# ESPRobotCar.net
KiCad netlist of a schematic drawn in EAGLE
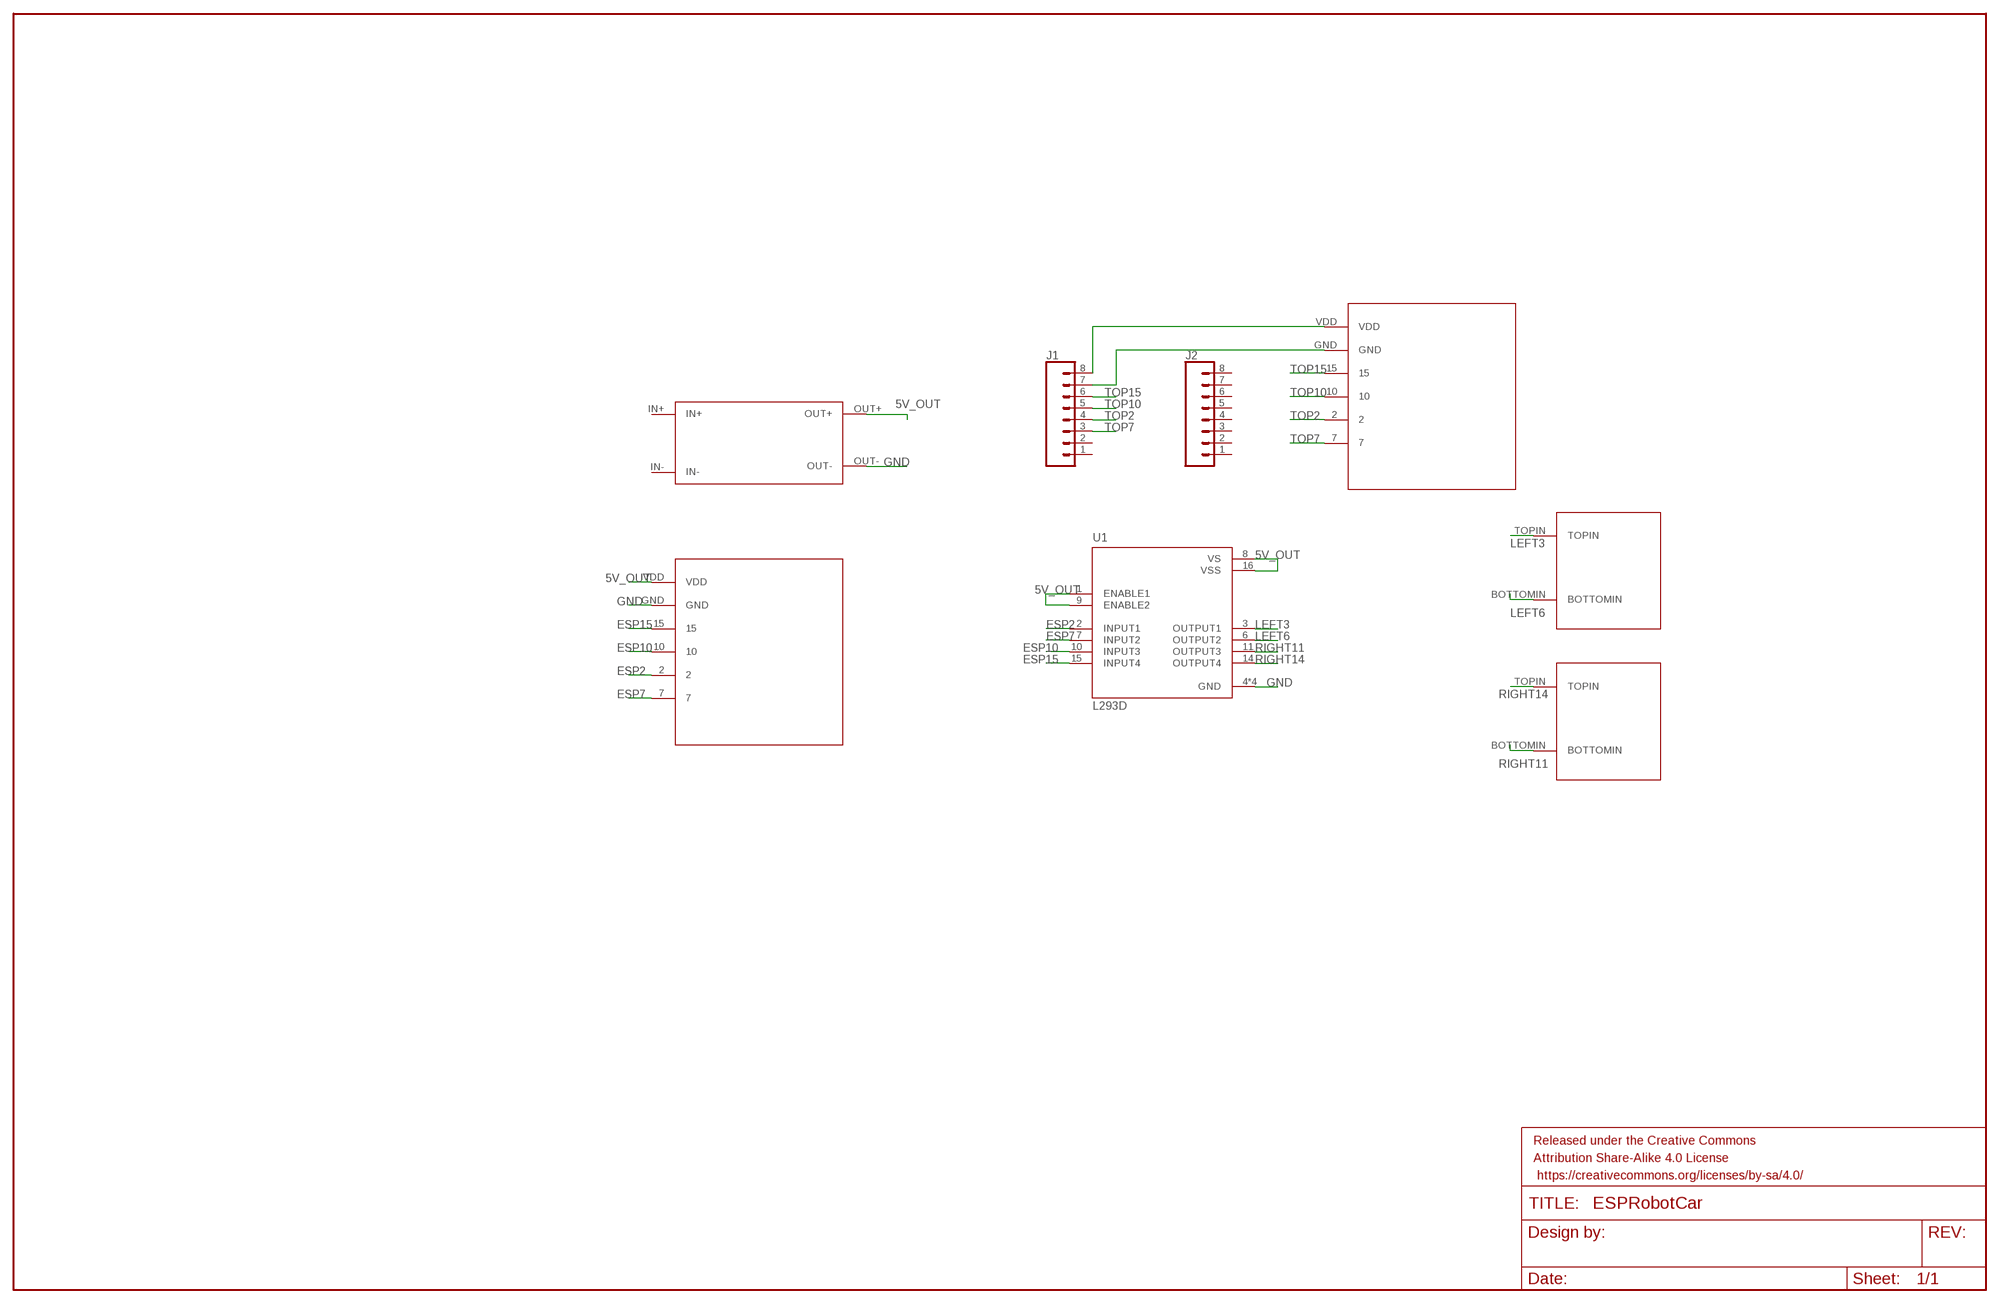
[diagram p0: schematic, sheet 1]

(export (version "E")
  (design (tool "Eeschema 10.0.6"))
  (components
    (comp (ref "FRAME1")
      (value "FRAME-LEDGER")
      (footprint "eagle-import:CREATIVE_COMMONS")
      (libsource (lib "eagle-import") (part "FRAME-LEDGER"))
    )
    (comp (ref "J1")
      (value "CONN_08\"")
      (footprint "eagle-import:1X08")
      (libsource (lib "eagle-import") (part "CONN_08{dblquote}"))
    )
    (comp (ref "J2")
      (value "CONN_08\"")
      (footprint "eagle-import:1X08")
      (libsource (lib "eagle-import") (part "CONN_08{dblquote}"))
    )
    (comp (ref "U$1")
      (value "DC_TO_DC")
      (footprint "eagle-import:DCTODC")
      (libsource (lib "eagle-import") (part "DC_TO_DC"))
    )
    (comp (ref "U$2")
      (value "MOTORPAD")
      (footprint "eagle-import:MOTORPAD")
      (libsource (lib "eagle-import") (part "MOTORPAD"))
    )
    (comp (ref "U$3")
      (value "MOTORPAD")
      (footprint "eagle-import:MOTORPAD")
      (libsource (lib "eagle-import") (part "MOTORPAD"))
    )
    (comp (ref "U$4")
      (value "MOTORBREAK")
      (footprint "eagle-import:MOTORBREAK")
      (libsource (lib "eagle-import") (part "MOTORBREAK"))
    )
    (comp (ref "U$5")
      (value "MOTORBREAK")
      (footprint "eagle-import:MOTORBREAK")
      (libsource (lib "eagle-import") (part "MOTORBREAK"))
    )
    (comp (ref "U1")
      (value "L293D")
      (footprint "eagle-import:DIP880W50P254L2000H510Q16")
      (fields (field (name "MF") "STMicroelectronics"))
      (libsource (lib "eagle-import") (part "L293D"))
    )
  )
  (nets
    (net (code "1") (name "/5V_OUT") (class "Default")
      (node (ref "U$1") (pin "OUT+") (pinfunction "OUT+_OUT+") (pintype "bidirectional"))
      (node (ref "U$4") (pin "VDD") (pinfunction "VDD_VDD") (pintype "bidirectional"))
      (node (ref "U1") (pin "1") (pinfunction "ENABLE1_1") (pintype "input"))
      (node (ref "U1") (pin "16") (pinfunction "VSS_16") (pintype "power_in"))
      (node (ref "U1") (pin "8") (pinfunction "VS_8") (pintype "power_in"))
      (node (ref "U1") (pin "9") (pinfunction "ENABLE2_9") (pintype "input"))
    )
    (net (code "2") (name "/ESP2") (class "Default")
      (node (ref "U$4") (pin "2") (pinfunction "2_2") (pintype "bidirectional"))
      (node (ref "U1") (pin "2") (pinfunction "INPUT1_2") (pintype "input"))
    )
    (net (code "3") (name "/ESP7") (class "Default")
      (node (ref "U$4") (pin "7") (pinfunction "7_7") (pintype "bidirectional"))
      (node (ref "U1") (pin "7") (pinfunction "INPUT2_7") (pintype "input"))
    )
    (net (code "4") (name "/ESP10") (class "Default")
      (node (ref "U$4") (pin "10") (pinfunction "10_10") (pintype "bidirectional"))
      (node (ref "U1") (pin "10") (pinfunction "INPUT3_10") (pintype "input"))
    )
    (net (code "5") (name "/ESP15") (class "Default")
      (node (ref "U$4") (pin "15") (pinfunction "15_15") (pintype "bidirectional"))
      (node (ref "U1") (pin "15") (pinfunction "INPUT4_15") (pintype "input"))
    )
    (net (code "6") (name "/GND") (class "Default")
      (node (ref "U$1") (pin "OUT-") (pinfunction "OUT-_OUT-") (pintype "bidirectional"))
      (node (ref "U$4") (pin "GND") (pinfunction "GND_GND") (pintype "bidirectional"))
      (node (ref "U1") (pin "12") (pinfunction "GND_12") (pintype "power_in"))
      (node (ref "U1") (pin "13") (pinfunction "GND_13") (pintype "power_in"))
      (node (ref "U1") (pin "4") (pinfunction "GND_4") (pintype "power_in"))
      (node (ref "U1") (pin "5") (pinfunction "GND_5") (pintype "power_in"))
    )
    (net (code "7") (name "/LEFT3") (class "Default")
      (node (ref "U$2") (pin "TOPIN") (pinfunction "TOPIN_TOPIN") (pintype "bidirectional"))
      (node (ref "U1") (pin "3") (pinfunction "OUTPUT1_3") (pintype "output"))
    )
    (net (code "8") (name "/LEFT6") (class "Default")
      (node (ref "U$2") (pin "BOTTOMIN") (pinfunction "BOTTOMIN_BOTTOMIN") (pintype "bidirectional"))
      (node (ref "U1") (pin "6") (pinfunction "OUTPUT2_6") (pintype "output"))
    )
    (net (code "9") (name "/RIGHT11") (class "Default")
      (node (ref "U$3") (pin "BOTTOMIN") (pinfunction "BOTTOMIN_BOTTOMIN") (pintype "bidirectional"))
      (node (ref "U1") (pin "11") (pinfunction "OUTPUT3_11") (pintype "output"))
    )
    (net (code "10") (name "/RIGHT14") (class "Default")
      (node (ref "U$3") (pin "TOPIN") (pinfunction "TOPIN_TOPIN") (pintype "bidirectional"))
      (node (ref "U1") (pin "14") (pinfunction "OUTPUT4_14") (pintype "output"))
    )
    (net (code "11") (name "/TOP2") (class "Default")
      (node (ref "J1") (pin "4") (pinfunction "4_4") (pintype "passive"))
      (node (ref "U$5") (pin "2") (pinfunction "2_2") (pintype "bidirectional"))
    )
    (net (code "12") (name "/TOP7") (class "Default")
      (node (ref "J1") (pin "3") (pinfunction "3_3") (pintype "passive"))
      (node (ref "U$5") (pin "7") (pinfunction "7_7") (pintype "bidirectional"))
    )
    (net (code "13") (name "/TOP10") (class "Default")
      (node (ref "J1") (pin "5") (pinfunction "5_5") (pintype "passive"))
      (node (ref "U$5") (pin "10") (pinfunction "10_10") (pintype "bidirectional"))
    )
    (net (code "14") (name "/TOP15") (class "Default")
      (node (ref "J1") (pin "6") (pinfunction "6_6") (pintype "passive"))
      (node (ref "U$5") (pin "15") (pinfunction "15_15") (pintype "bidirectional"))
    )
    (net (code "15") (name "Net-(J1-Pad7)") (class "Default")
      (node (ref "J1") (pin "7") (pinfunction "7_7") (pintype "passive"))
      (node (ref "U$5") (pin "GND") (pinfunction "GND_GND") (pintype "bidirectional"))
    )
    (net (code "16") (name "Net-(J1-Pad8)") (class "Default")
      (node (ref "J1") (pin "8") (pinfunction "8_8") (pintype "passive"))
      (node (ref "U$5") (pin "VDD") (pinfunction "VDD_VDD") (pintype "bidirectional"))
    )
    (net (code "17") (name "unconnected-(J1-Pad1)") (class "Default")
      (node (ref "J1") (pin "1") (pinfunction "1_1") (pintype "passive"))
    )
    (net (code "18") (name "unconnected-(J1-Pad2)") (class "Default")
      (node (ref "J1") (pin "2") (pinfunction "2_2") (pintype "passive"))
    )
    (net (code "19") (name "unconnected-(J2-Pad1)") (class "Default")
      (node (ref "J2") (pin "1") (pinfunction "1_1") (pintype "passive"))
    )
    (net (code "20") (name "unconnected-(J2-Pad2)") (class "Default")
      (node (ref "J2") (pin "2") (pinfunction "2_2") (pintype "passive"))
    )
    (net (code "21") (name "unconnected-(J2-Pad3)") (class "Default")
      (node (ref "J2") (pin "3") (pinfunction "3_3") (pintype "passive"))
    )
    (net (code "22") (name "unconnected-(J2-Pad4)") (class "Default")
      (node (ref "J2") (pin "4") (pinfunction "4_4") (pintype "passive"))
    )
    (net (code "23") (name "unconnected-(J2-Pad5)") (class "Default")
      (node (ref "J2") (pin "5") (pinfunction "5_5") (pintype "passive"))
    )
    (net (code "24") (name "unconnected-(J2-Pad6)") (class "Default")
      (node (ref "J2") (pin "6") (pinfunction "6_6") (pintype "passive"))
    )
    (net (code "25") (name "unconnected-(J2-Pad7)") (class "Default")
      (node (ref "J2") (pin "7") (pinfunction "7_7") (pintype "passive"))
    )
    (net (code "26") (name "unconnected-(J2-Pad8)") (class "Default")
      (node (ref "J2") (pin "8") (pinfunction "8_8") (pintype "passive"))
    )
    (net (code "27") (name "unconnected-(U$1-PadIN+)") (class "Default")
      (node (ref "U$1") (pin "IN+") (pinfunction "IN+_IN+") (pintype "bidirectional"))
    )
    (net (code "28") (name "unconnected-(U$1-PadIN-)") (class "Default")
      (node (ref "U$1") (pin "IN-") (pinfunction "IN-_IN-") (pintype "bidirectional"))
    )
  )
)
